# IBus_BMW_DAC_Test.net
KiCad netlist of a schematic drawn in EasyEDA
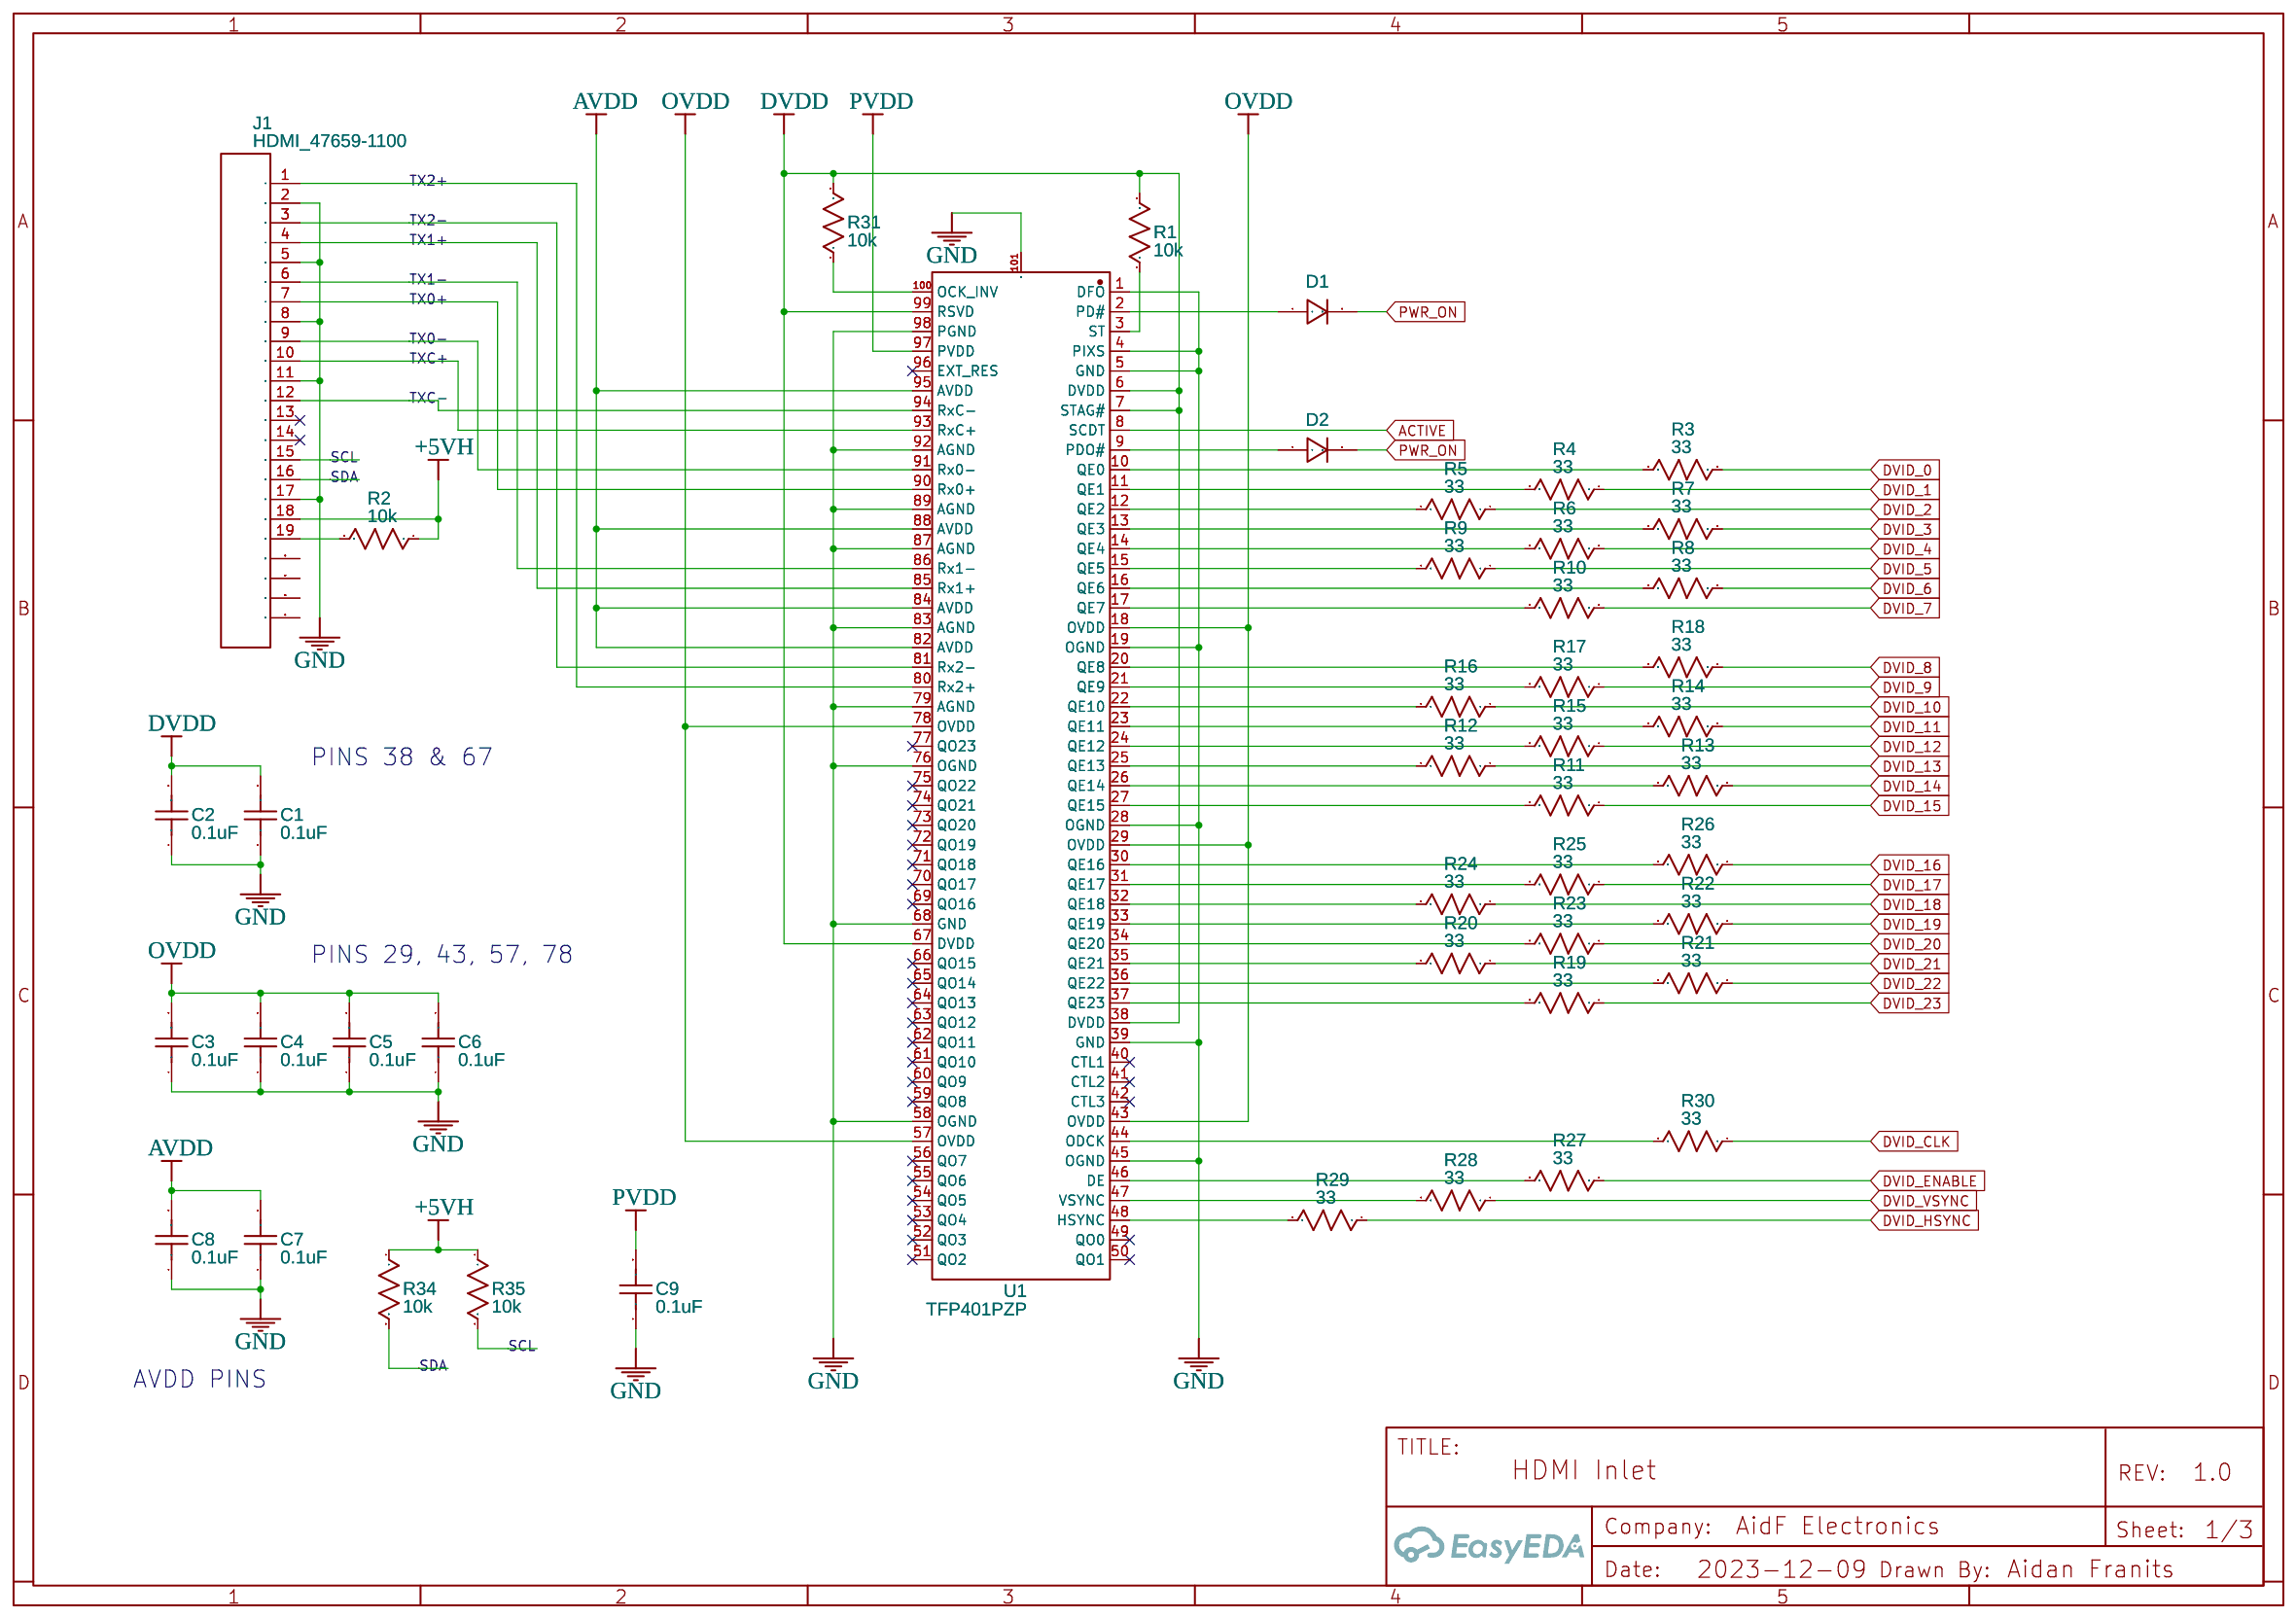
[diagram p0: HDMI Inlet]
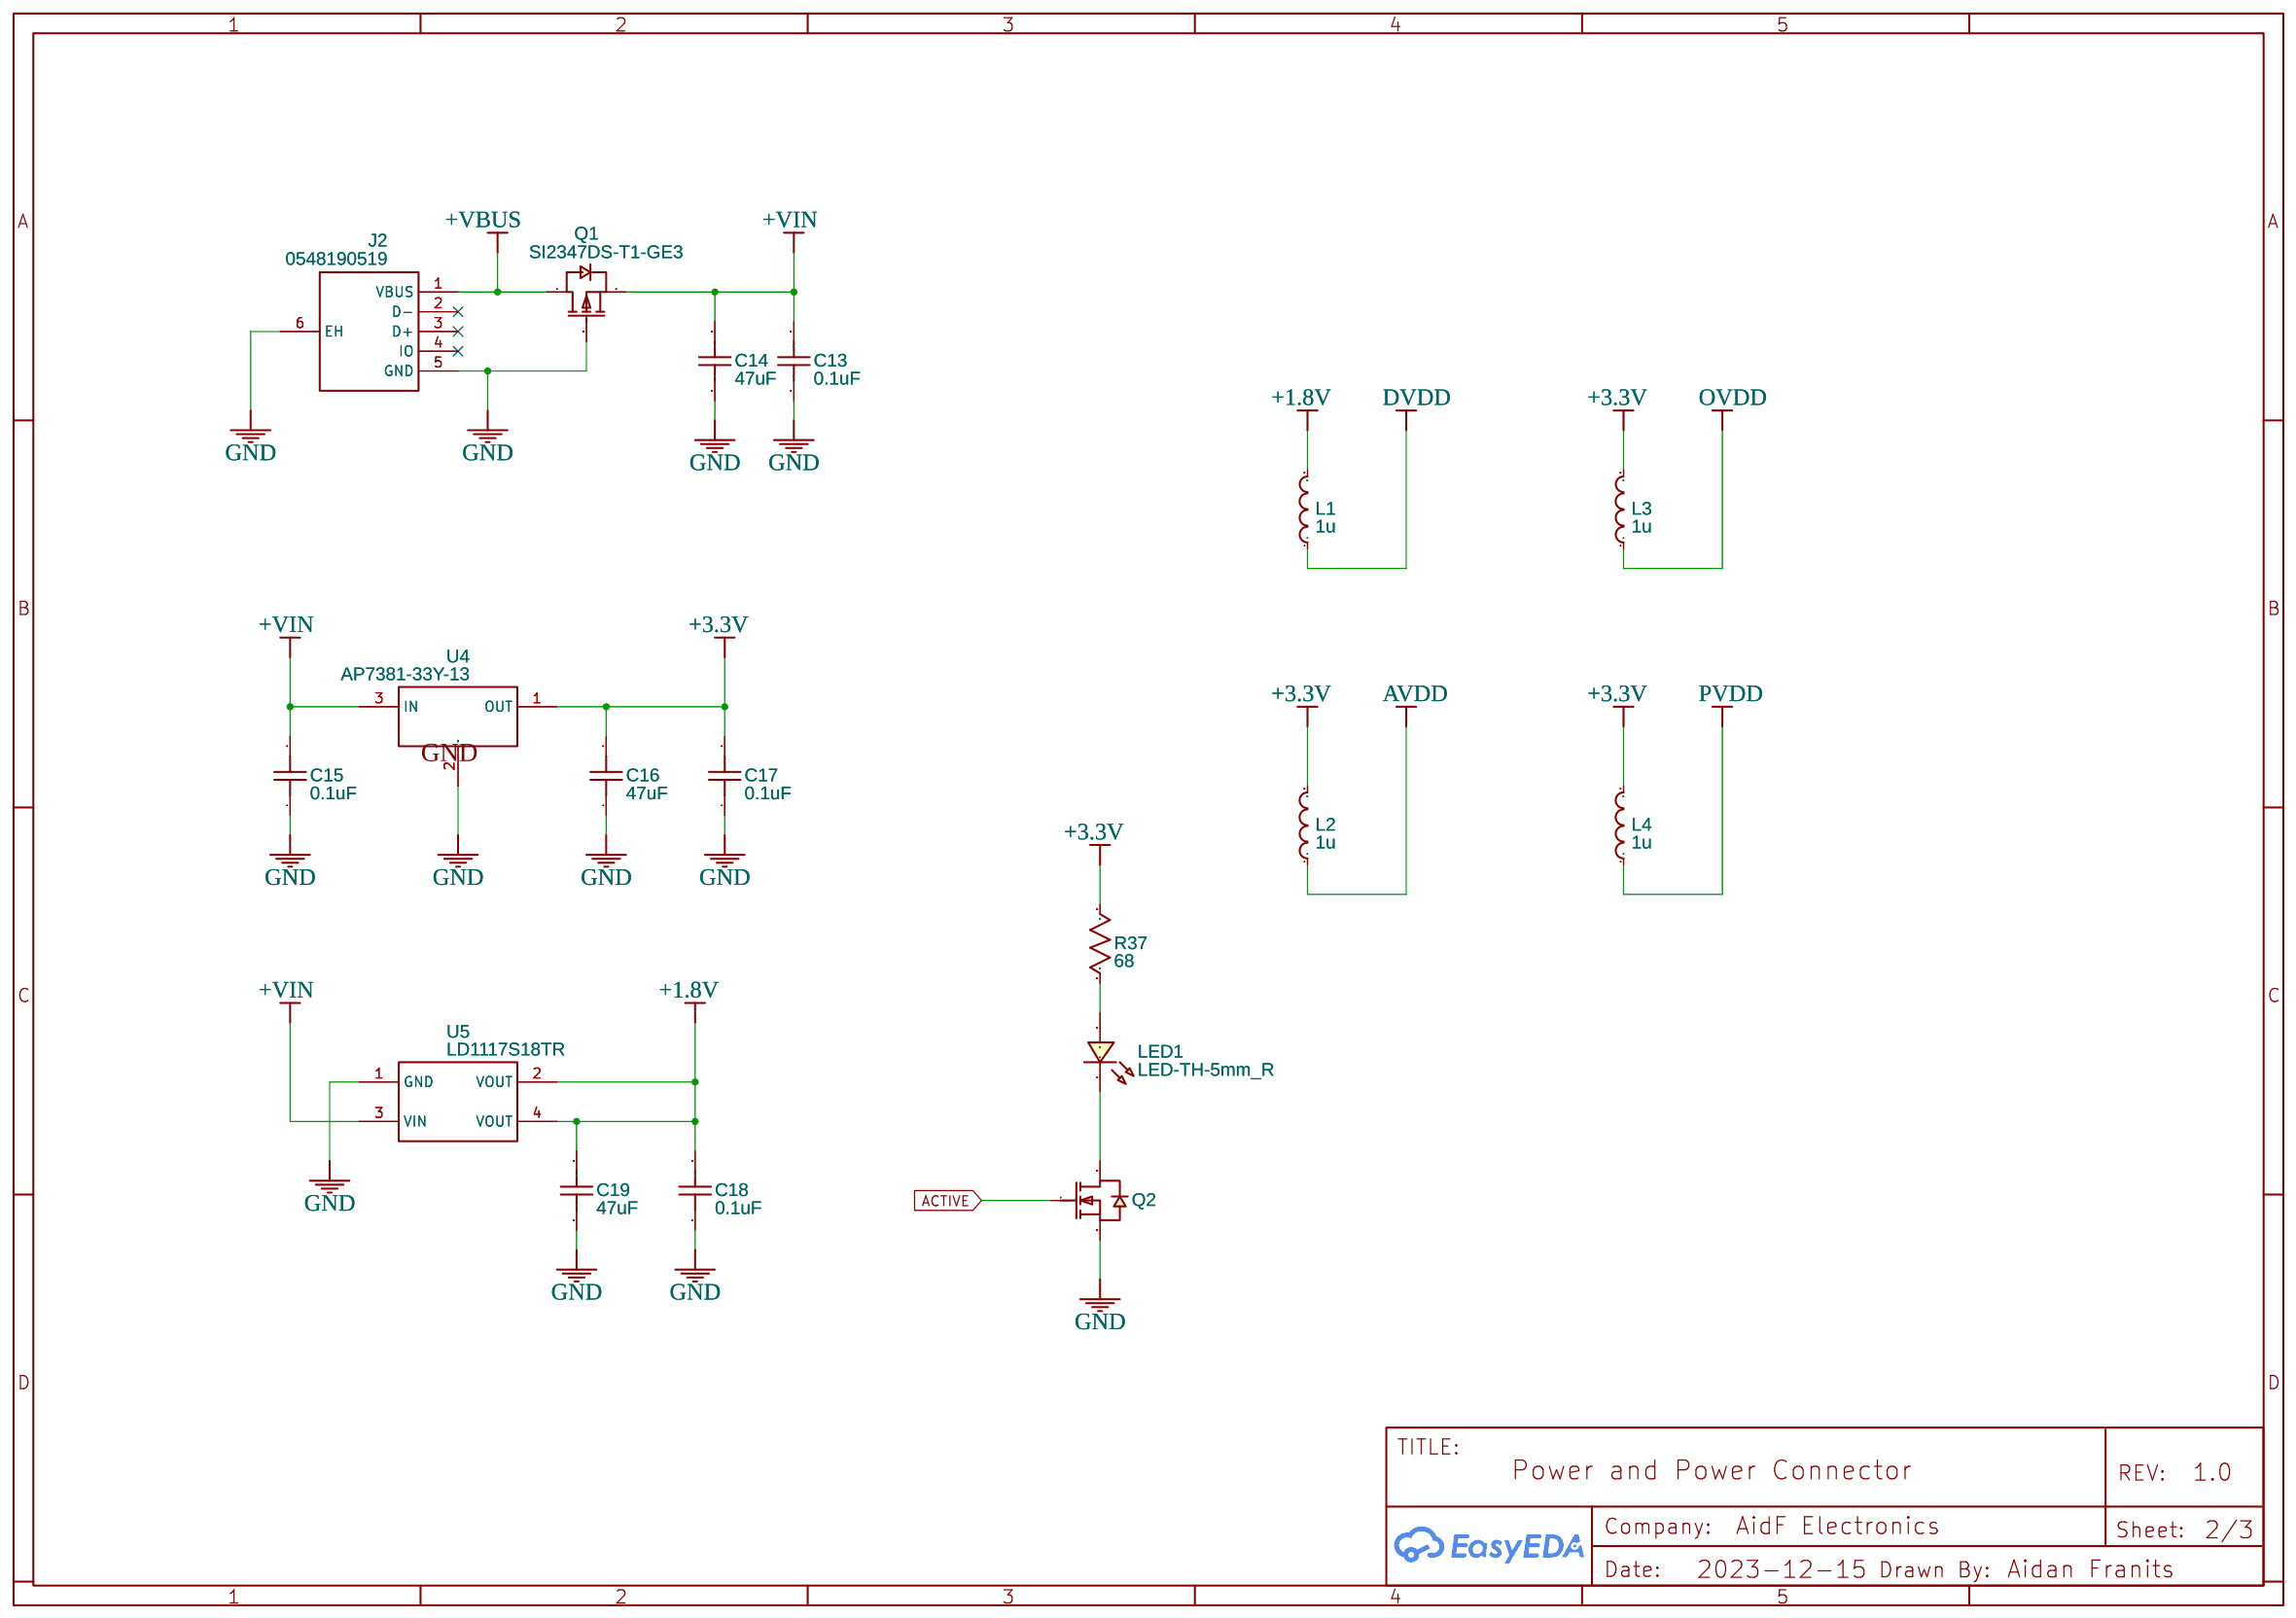
[diagram p1: Power and Power Connector]
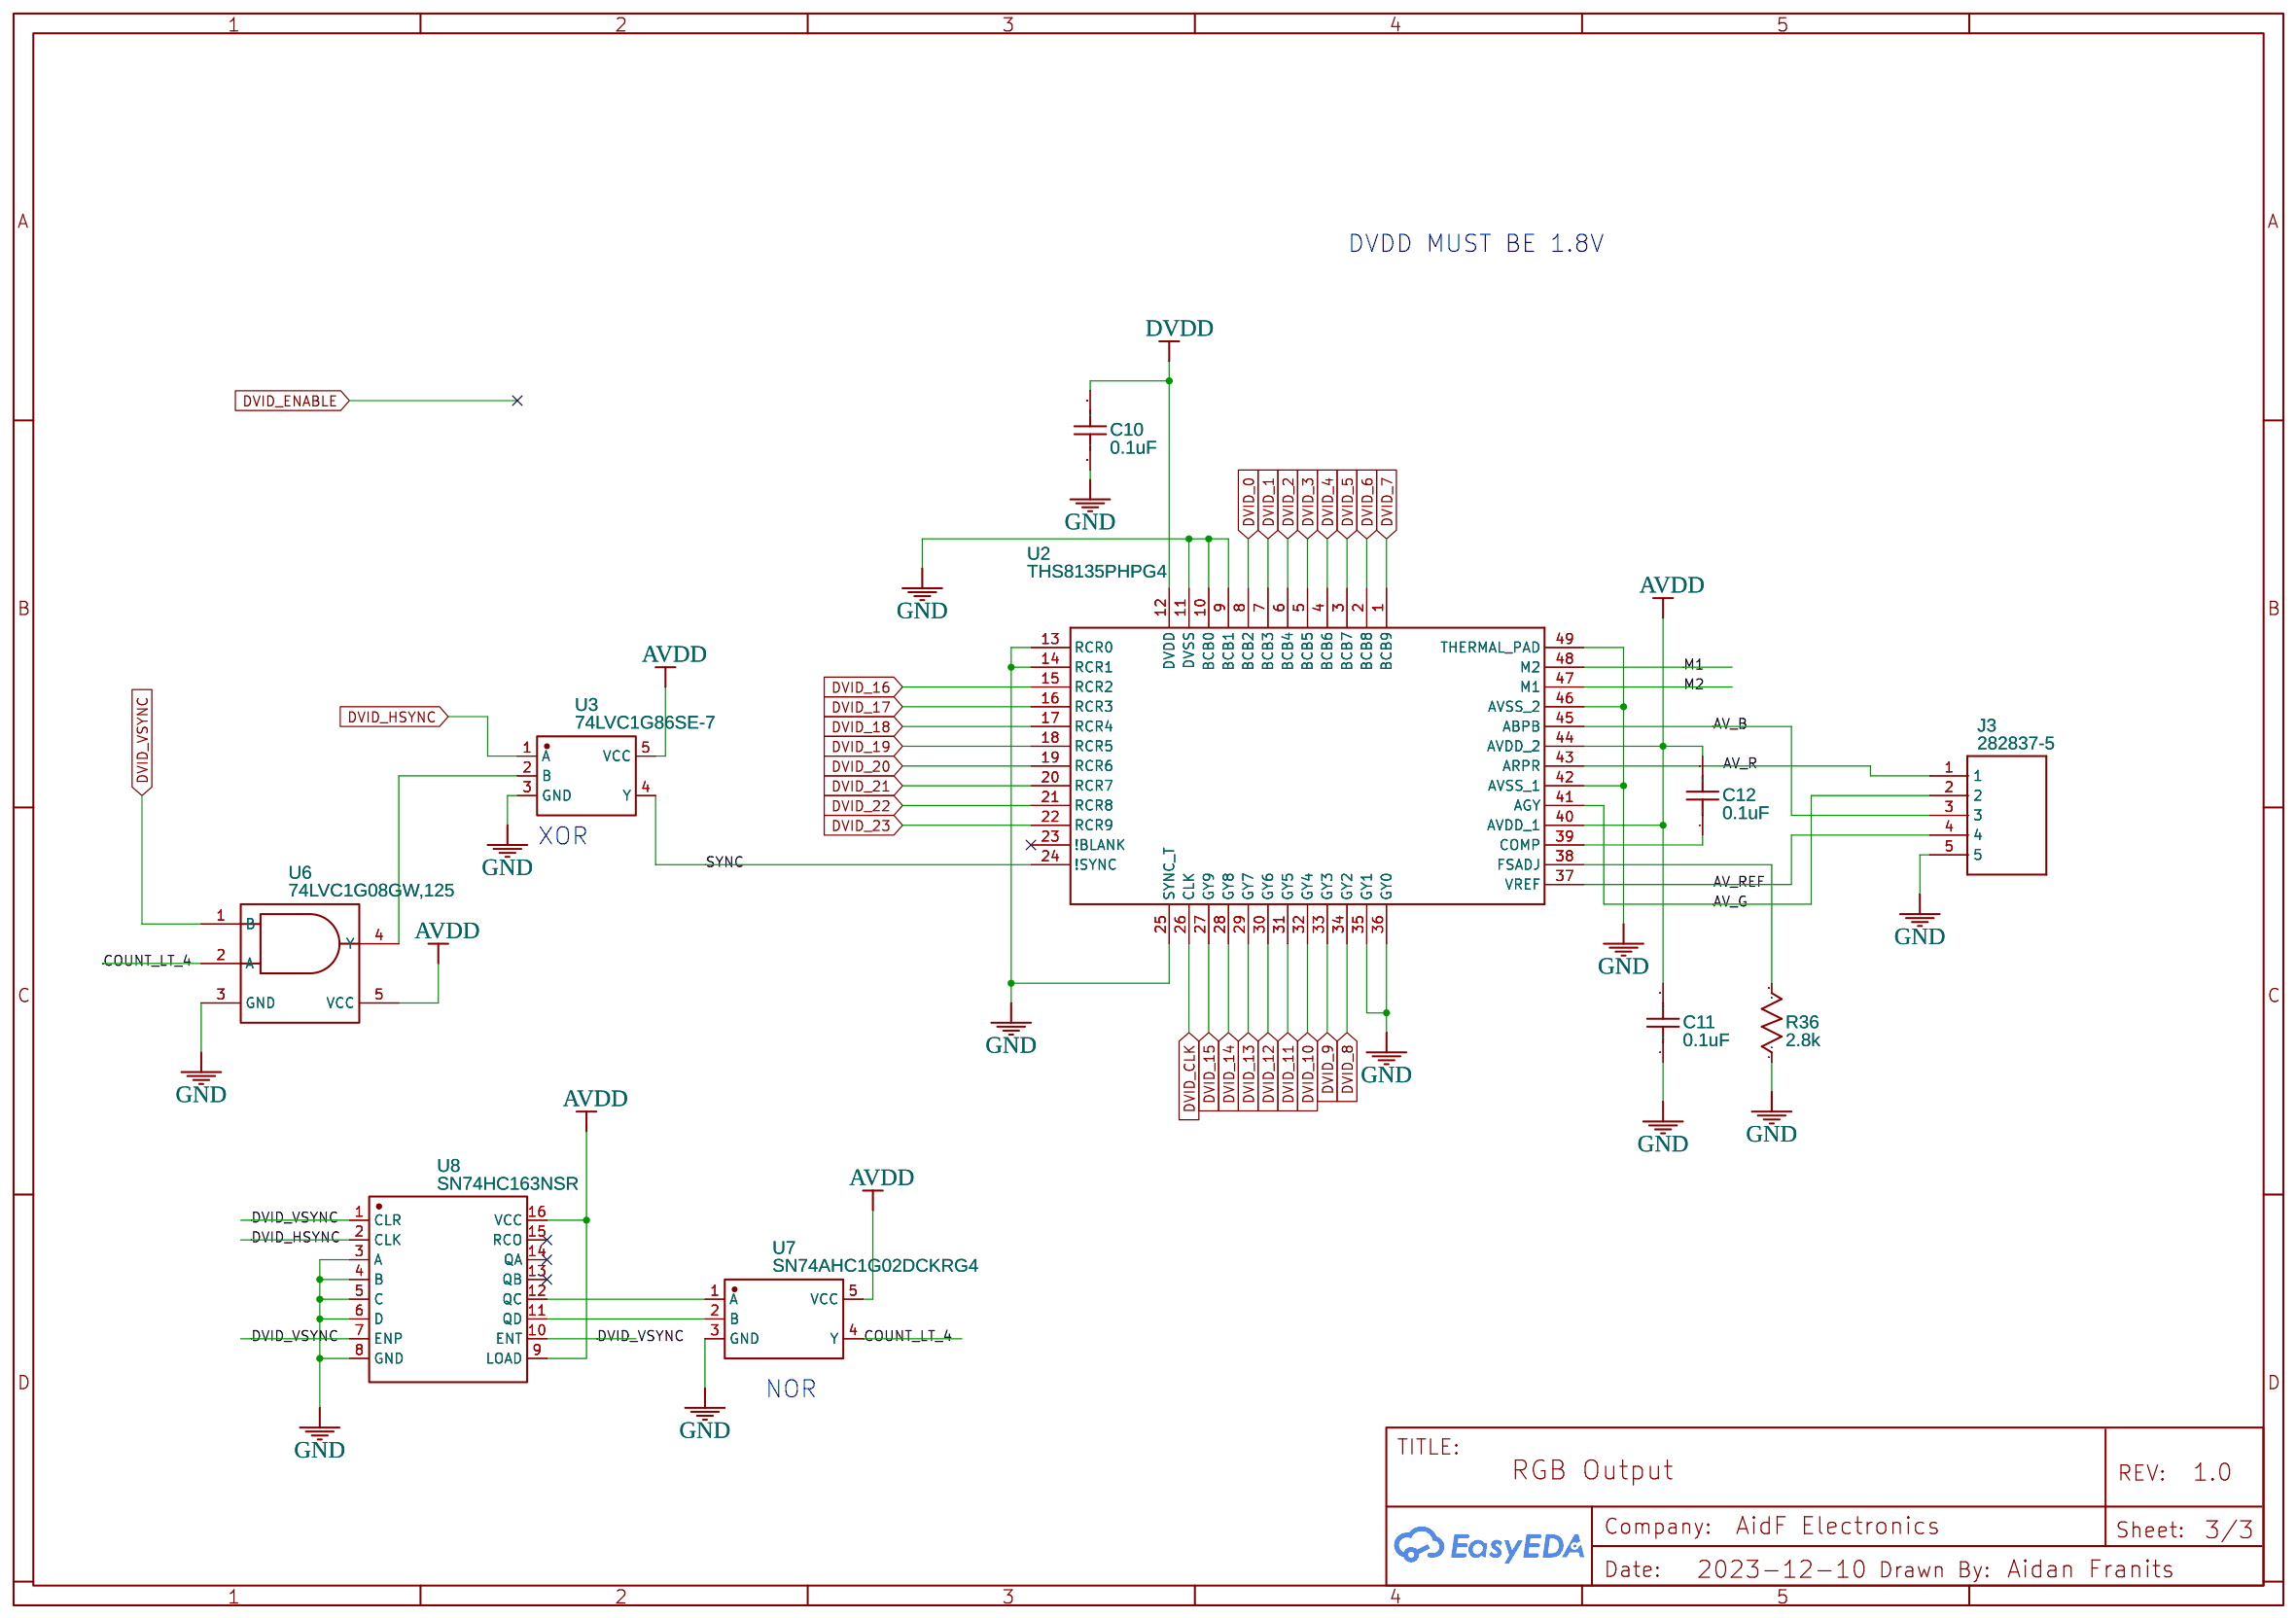
[diagram p2: RGB Output]

(export (version "E")
  (design (tool "Eeschema 10.0.6"))
  (components
    (comp (ref "C1")
      (value "0.1uF")
      (fields
        (field (name "Manufacturer Part") "0603B104K101CT")
        (field (name "Manufacturer") "Walsin Technology Corporation")
      )
      (libsource (lib "") (part "C_0603_US"))
    )
    (comp (ref "C2")
      (value "0.1uF")
      (fields
        (field (name "Manufacturer Part") "0603B104K101CT")
        (field (name "Manufacturer") "Walsin Technology Corporation")
      )
      (libsource (lib "") (part "C_0603_US"))
    )
    (comp (ref "C3")
      (value "0.1uF")
      (fields
        (field (name "Manufacturer Part") "0603B104K101CT")
        (field (name "Manufacturer") "Walsin Technology Corporation")
      )
      (libsource (lib "") (part "C_0603_US"))
    )
    (comp (ref "C4")
      (value "0.1uF")
      (fields
        (field (name "Manufacturer Part") "0603B104K101CT")
        (field (name "Manufacturer") "Walsin Technology Corporation")
      )
      (libsource (lib "") (part "C_0603_US"))
    )
    (comp (ref "C5")
      (value "0.1uF")
      (fields
        (field (name "Manufacturer Part") "0603B104K101CT")
        (field (name "Manufacturer") "Walsin Technology Corporation")
      )
      (libsource (lib "") (part "C_0603_US"))
    )
    (comp (ref "C6")
      (value "0.1uF")
      (fields
        (field (name "Manufacturer Part") "0603B104K101CT")
        (field (name "Manufacturer") "Walsin Technology Corporation")
      )
      (libsource (lib "") (part "C_0603_US"))
    )
    (comp (ref "C7")
      (value "0.1uF")
      (fields
        (field (name "Manufacturer Part") "0603B104K101CT")
        (field (name "Manufacturer") "Walsin Technology Corporation")
      )
      (libsource (lib "") (part "C_0603_US"))
    )
    (comp (ref "C8")
      (value "0.1uF")
      (fields
        (field (name "Manufacturer Part") "0603B104K101CT")
        (field (name "Manufacturer") "Walsin Technology Corporation")
      )
      (libsource (lib "") (part "C_0603_US"))
    )
    (comp (ref "C9")
      (value "0.1uF")
      (fields
        (field (name "Manufacturer Part") "0603B104K101CT")
        (field (name "Manufacturer") "Walsin Technology Corporation")
      )
      (libsource (lib "") (part "C_0603_US"))
    )
    (comp (ref "D1")
      (value "SD103AWS-TP")
      (fields (field (name "Manufacturer") "Micro Commercial Co"))
      (libsource (lib "") (part "1N4148"))
    )
    (comp (ref "D2")
      (value "SD103AWS-TP")
      (fields (field (name "Manufacturer") "Micro Commercial Co"))
      (libsource (lib "") (part "1N4148"))
    )
    (comp (ref "J1")
      (value "HDMI_47659-1100")
      (fields (field (name "Manufacturer Part") "2086581051") (field (name "Manufacturer") "Molex"))
      (libsource (lib "") (part "HDMI_47659-1100"))
    )
    (comp (ref "R1")
      (value "10k")
      (fields
        (field (name "Manufacturer Part") "ESR03EZPJ103")
        (field (name "Manufacturer") "Rohm Semiconductor")
      )
      (libsource (lib "") (part "R_0603_US_1"))
    )
    (comp (ref "R2")
      (value "10k")
      (fields
        (field (name "Manufacturer Part") "ESR03EZPJ103")
        (field (name "Manufacturer") "Rohm Semiconductor")
      )
      (libsource (lib "") (part "R_0603_US"))
    )
    (comp (ref "R3")
      (value "33")
      (fields
        (field (name "Manufacturer Part") "WR06X330 JTL")
        (field (name "Manufacturer") "Walsin Technology Corporation")
      )
      (libsource (lib "") (part "R_0603_US"))
    )
    (comp (ref "R4")
      (value "33")
      (fields
        (field (name "Manufacturer Part") "WR06X330 JTL")
        (field (name "Manufacturer") "Walsin Technology Corporation")
      )
      (libsource (lib "") (part "R_0603_US"))
    )
    (comp (ref "R5")
      (value "33")
      (fields
        (field (name "Manufacturer Part") "WR06X330 JTL")
        (field (name "Manufacturer") "Walsin Technology Corporation")
      )
      (libsource (lib "") (part "R_0603_US"))
    )
    (comp (ref "R6")
      (value "33")
      (fields
        (field (name "Manufacturer Part") "WR06X330 JTL")
        (field (name "Manufacturer") "Walsin Technology Corporation")
      )
      (libsource (lib "") (part "R_0603_US"))
    )
    (comp (ref "R7")
      (value "33")
      (fields
        (field (name "Manufacturer Part") "WR06X330 JTL")
        (field (name "Manufacturer") "Walsin Technology Corporation")
      )
      (libsource (lib "") (part "R_0603_US"))
    )
    (comp (ref "R8")
      (value "33")
      (fields
        (field (name "Manufacturer Part") "WR06X330 JTL")
        (field (name "Manufacturer") "Walsin Technology Corporation")
      )
      (libsource (lib "") (part "R_0603_US"))
    )
    (comp (ref "R9")
      (value "33")
      (fields
        (field (name "Manufacturer Part") "WR06X330 JTL")
        (field (name "Manufacturer") "Walsin Technology Corporation")
      )
      (libsource (lib "") (part "R_0603_US"))
    )
    (comp (ref "R10")
      (value "33")
      (fields
        (field (name "Manufacturer Part") "WR06X330 JTL")
        (field (name "Manufacturer") "Walsin Technology Corporation")
      )
      (libsource (lib "") (part "R_0603_US"))
    )
    (comp (ref "R11")
      (value "33")
      (fields
        (field (name "Manufacturer Part") "WR06X330 JTL")
        (field (name "Manufacturer") "Walsin Technology Corporation")
      )
      (libsource (lib "") (part "R_0603_US"))
    )
    (comp (ref "R12")
      (value "33")
      (fields
        (field (name "Manufacturer Part") "WR06X330 JTL")
        (field (name "Manufacturer") "Walsin Technology Corporation")
      )
      (libsource (lib "") (part "R_0603_US"))
    )
    (comp (ref "R13")
      (value "33")
      (fields
        (field (name "Manufacturer Part") "WR06X330 JTL")
        (field (name "Manufacturer") "Walsin Technology Corporation")
      )
      (libsource (lib "") (part "R_0603_US"))
    )
    (comp (ref "R14")
      (value "33")
      (fields
        (field (name "Manufacturer Part") "WR06X330 JTL")
        (field (name "Manufacturer") "Walsin Technology Corporation")
      )
      (libsource (lib "") (part "R_0603_US"))
    )
    (comp (ref "R15")
      (value "33")
      (fields
        (field (name "Manufacturer Part") "WR06X330 JTL")
        (field (name "Manufacturer") "Walsin Technology Corporation")
      )
      (libsource (lib "") (part "R_0603_US"))
    )
    (comp (ref "R16")
      (value "33")
      (fields
        (field (name "Manufacturer Part") "WR06X330 JTL")
        (field (name "Manufacturer") "Walsin Technology Corporation")
      )
      (libsource (lib "") (part "R_0603_US"))
    )
    (comp (ref "R17")
      (value "33")
      (fields
        (field (name "Manufacturer Part") "WR06X330 JTL")
        (field (name "Manufacturer") "Walsin Technology Corporation")
      )
      (libsource (lib "") (part "R_0603_US"))
    )
    (comp (ref "R18")
      (value "33")
      (fields
        (field (name "Manufacturer Part") "WR06X330 JTL")
        (field (name "Manufacturer") "Walsin Technology Corporation")
      )
      (libsource (lib "") (part "R_0603_US"))
    )
    (comp (ref "R19")
      (value "33")
      (fields
        (field (name "Manufacturer Part") "WR06X330 JTL")
        (field (name "Manufacturer") "Walsin Technology Corporation")
      )
      (libsource (lib "") (part "R_0603_US"))
    )
    (comp (ref "R20")
      (value "33")
      (fields
        (field (name "Manufacturer Part") "WR06X330 JTL")
        (field (name "Manufacturer") "Walsin Technology Corporation")
      )
      (libsource (lib "") (part "R_0603_US"))
    )
    (comp (ref "R21")
      (value "33")
      (fields
        (field (name "Manufacturer Part") "WR06X330 JTL")
        (field (name "Manufacturer") "Walsin Technology Corporation")
      )
      (libsource (lib "") (part "R_0603_US"))
    )
    (comp (ref "R22")
      (value "33")
      (fields
        (field (name "Manufacturer Part") "WR06X330 JTL")
        (field (name "Manufacturer") "Walsin Technology Corporation")
      )
      (libsource (lib "") (part "R_0603_US"))
    )
    (comp (ref "R23")
      (value "33")
      (fields
        (field (name "Manufacturer Part") "WR06X330 JTL")
        (field (name "Manufacturer") "Walsin Technology Corporation")
      )
      (libsource (lib "") (part "R_0603_US"))
    )
    (comp (ref "R24")
      (value "33")
      (fields
        (field (name "Manufacturer Part") "WR06X330 JTL")
        (field (name "Manufacturer") "Walsin Technology Corporation")
      )
      (libsource (lib "") (part "R_0603_US"))
    )
    (comp (ref "R25")
      (value "33")
      (fields
        (field (name "Manufacturer Part") "WR06X330 JTL")
        (field (name "Manufacturer") "Walsin Technology Corporation")
      )
      (libsource (lib "") (part "R_0603_US"))
    )
    (comp (ref "R26")
      (value "33")
      (fields
        (field (name "Manufacturer Part") "WR06X330 JTL")
        (field (name "Manufacturer") "Walsin Technology Corporation")
      )
      (libsource (lib "") (part "R_0603_US"))
    )
    (comp (ref "R27")
      (value "33")
      (fields
        (field (name "Manufacturer Part") "WR06X330 JTL")
        (field (name "Manufacturer") "Walsin Technology Corporation")
      )
      (libsource (lib "") (part "R_0603_US"))
    )
    (comp (ref "R28")
      (value "33")
      (fields
        (field (name "Manufacturer Part") "WR06X330 JTL")
        (field (name "Manufacturer") "Walsin Technology Corporation")
      )
      (libsource (lib "") (part "R_0603_US"))
    )
    (comp (ref "R29")
      (value "33")
      (fields
        (field (name "Manufacturer Part") "WR06X330 JTL")
        (field (name "Manufacturer") "Walsin Technology Corporation")
      )
      (libsource (lib "") (part "R_0603_US"))
    )
    (comp (ref "R30")
      (value "33")
      (fields
        (field (name "Manufacturer Part") "WR06X330 JTL")
        (field (name "Manufacturer") "Walsin Technology Corporation")
      )
      (libsource (lib "") (part "R_0603_US"))
    )
    (comp (ref "R31")
      (value "10k")
      (fields
        (field (name "Manufacturer Part") "ESR03EZPJ103")
        (field (name "Manufacturer") "Rohm Semiconductor")
      )
      (libsource (lib "") (part "R_0603_US_1"))
    )
    (comp (ref "R34")
      (value "10k")
      (fields
        (field (name "Manufacturer Part") "ESR03EZPJ103")
        (field (name "Manufacturer") "Rohm Semiconductor")
      )
      (libsource (lib "") (part "R_0603_US_2"))
    )
    (comp (ref "R35")
      (value "10k")
      (fields
        (field (name "Manufacturer Part") "ESR03EZPJ103")
        (field (name "Manufacturer") "Rohm Semiconductor")
      )
      (libsource (lib "") (part "R_0603_US_2"))
    )
    (comp (ref "U1")
      (value "TFP401PZP")
      (fields (field (name "Manufacturer") "Texas Instruments"))
      (libsource (lib "") (part "TFP401PZP"))
    )
    (comp (ref "C13")
      (value "0.1uF")
      (fields
        (field (name "Manufacturer Part") "0603B104K101CT")
        (field (name "Manufacturer") "Walsin Technology Corporation")
      )
      (libsource (lib "") (part "C_0603_US"))
    )
    (comp (ref "C14")
      (value "47uF")
      (fields
        (field (name "Manufacturer Part") "GRM31CR61E476ME44K")
        (field (name "Manufacturer") "Murata Electronics")
      )
      (libsource (lib "") (part "C_0603_US"))
    )
    (comp (ref "C15")
      (value "0.1uF")
      (fields
        (field (name "Manufacturer Part") "0603B104K101CT")
        (field (name "Manufacturer") "Walsin Technology Corporation")
      )
      (libsource (lib "") (part "C_0603_US"))
    )
    (comp (ref "C16")
      (value "47uF")
      (fields
        (field (name "Manufacturer Part") "GRM31CR61E476ME44K")
        (field (name "Manufacturer") "Murata Electronics")
      )
      (libsource (lib "") (part "C_0603_US"))
    )
    (comp (ref "C17")
      (value "0.1uF")
      (fields
        (field (name "Manufacturer Part") "0603B104K101CT")
        (field (name "Manufacturer") "Walsin Technology Corporation")
      )
      (libsource (lib "") (part "C_0603_US"))
    )
    (comp (ref "C18")
      (value "0.1uF")
      (fields
        (field (name "Manufacturer Part") "0603B104K101CT")
        (field (name "Manufacturer") "Walsin Technology Corporation")
      )
      (libsource (lib "") (part "C_0603_US"))
    )
    (comp (ref "C19")
      (value "47uF")
      (fields
        (field (name "Manufacturer Part") "GRM31CR61E476ME44K")
        (field (name "Manufacturer") "Murata Electronics")
      )
      (libsource (lib "") (part "C_0603_US"))
    )
    (comp (ref "J2")
      (value "0548190519")
      (fields (field (name "Manufacturer") "Molex"))
      (libsource (lib "") (part "0548190519"))
    )
    (comp (ref "L1")
      (value "1u")
      (fields
        (field (name "Manufacturer Part") "BLM18RK601SN1D")
        (field (name "Manufacturer") "Murata Electronics")
      )
      (libsource (lib "") (part "L0603_US_1"))
    )
    (comp (ref "L2")
      (value "1u")
      (fields
        (field (name "Manufacturer Part") "BLM18RK601SN1D")
        (field (name "Manufacturer") "Murata Electronics")
      )
      (libsource (lib "") (part "L0603_US"))
    )
    (comp (ref "L3")
      (value "1u")
      (fields
        (field (name "Manufacturer Part") "BLM18RK601SN1D")
        (field (name "Manufacturer") "Murata Electronics")
      )
      (libsource (lib "") (part "L0603_US_1"))
    )
    (comp (ref "L4")
      (value "1u")
      (fields
        (field (name "Manufacturer Part") "BLM18RK601SN1D")
        (field (name "Manufacturer") "Murata Electronics")
      )
      (libsource (lib "") (part "L0603_US"))
    )
    (comp (ref "LED1") (value "LED-TH-5mm_R") (libsource (lib "") (part "LED-TH-5mm_R")))
    (comp (ref "Q1")
      (value "SI2347DS-T1-GE3")
      (fields (field (name "Manufacturer") "Vishay Siliconix"))
      (libsource (lib "") (part "IRF5210"))
    )
    (comp (ref "Q2")
      (value "DMN67D8LW-13")
      (fields (field (name "Manufacturer") "Diodes Incorporated"))
      (libsource (lib "") (part "2N7002"))
    )
    (comp (ref "R37")
      (value "68")
      (fields
        (field (name "Manufacturer Part") "WR06X680 JTL")
        (field (name "Manufacturer") "Walsin Technology Corporation")
      )
      (libsource (lib "") (part "R_0603_US"))
    )
    (comp (ref "U4")
      (value "AP7381-33Y-13")
      (fields
        (field (name "Manufacturer Part") "AP7370-33Y-13")
        (field (name "Manufacturer") "Diodes Incorporated")
      )
      (libsource (lib "") (part "AP7381-33Y-13"))
    )
    (comp (ref "U5")
      (value "LD1117S18TR")
      (fields (field (name "Manufacturer") "STMicroelectronics"))
      (libsource (lib "") (part "LD1117S18TR"))
    )
    (comp (ref "C10")
      (value "0.1uF")
      (fields
        (field (name "Manufacturer Part") "0603B104K101CT")
        (field (name "Manufacturer") "Walsin Technology Corporation")
      )
      (libsource (lib "") (part "C_0603_US"))
    )
    (comp (ref "C11")
      (value "0.1uF")
      (fields
        (field (name "Manufacturer Part") "0603B104K101CT")
        (field (name "Manufacturer") "Walsin Technology Corporation")
      )
      (libsource (lib "") (part "C_0603_US"))
    )
    (comp (ref "C12")
      (value "0.1uF")
      (fields
        (field (name "Manufacturer Part") "0603B104K101CT")
        (field (name "Manufacturer") "Walsin Technology Corporation")
      )
      (libsource (lib "") (part "C_0603_US"))
    )
    (comp (ref "J3")
      (value "282837-5")
      (fields (field (name "Manufacturer") "TE Connectivity AMP Connectors"))
      (libsource (lib "") (part "282837-5"))
    )
    (comp (ref "R36")
      (value "2.8k")
      (fields
        (field (name "Manufacturer Part") "RMCF0603FT2K80")
        (field (name "Manufacturer") "Stackpole Electronics Inc")
      )
      (libsource (lib "") (part "R_0603_US"))
    )
    (comp (ref "U2")
      (value "THS8135PHPG4")
      (fields
        (field (name "Manufacturer Part") "THS8135PHP")
        (field (name "Manufacturer") "Texas Instruments")
      )
      (libsource (lib "") (part "THS8135PHPG4"))
    )
    (comp (ref "U3")
      (value "74LVC1G86SE-7")
      (fields (field (name "Manufacturer") "Diodes Incorporated"))
      (libsource (lib "") (part "74LVC1G86SE-7"))
    )
    (comp (ref "U6")
      (value "74LVC1G08GW,125")
      (fields (field (name "Manufacturer") "Nexperia USA Inc."))
      (libsource (lib "") (part "74LVC1G08GW,125"))
    )
    (comp (ref "U7")
      (value "SN74AHC1G02DCKRG4")
      (fields (field (name "Manufacturer") "TI(德州仪器)"))
      (libsource (lib "") (part "SN74AHC1G02DCKRG4"))
    )
    (comp (ref "U8")
      (value "SN74HC163NSR")
      (fields (field (name "Manufacturer") "Texas Instruments"))
      (libsource (lib "") (part "SN74HC163NSR"))
    )
  )
  (nets
    (net (code "1") (name "+1.8V") (class "Default")
      (node (ref "C18") (pin "2") (pinfunction "2_2") (pintype "unspecified"))
      (node (ref "C19") (pin "2") (pinfunction "2_2") (pintype "unspecified"))
      (node (ref "L1") (pin "2") (pinfunction "2_2") (pintype "unspecified"))
      (node (ref "U5") (pin "2") (pinfunction "VOUT_2") (pintype "unspecified"))
      (node (ref "U5") (pin "4") (pinfunction "VOUT_4") (pintype "unspecified"))
    )
    (net (code "2") (name "+3.3V") (class "Default")
      (node (ref "C16") (pin "2") (pinfunction "2_2") (pintype "unspecified"))
      (node (ref "C17") (pin "2") (pinfunction "2_2") (pintype "unspecified"))
      (node (ref "L2") (pin "2") (pinfunction "2_2") (pintype "unspecified"))
      (node (ref "L3") (pin "2") (pinfunction "2_2") (pintype "unspecified"))
      (node (ref "L4") (pin "2") (pinfunction "2_2") (pintype "unspecified"))
      (node (ref "R37") (pin "1") (pinfunction "1_1") (pintype "unspecified"))
      (node (ref "U4") (pin "1") (pinfunction "OUT_1") (pintype "passive"))
    )
    (net (code "3") (name "+5VH") (class "Default")
      (node (ref "J1") (pin "18") (pinfunction "18_18") (pintype "bidirectional"))
      (node (ref "R2") (pin "1") (pinfunction "1_1") (pintype "unspecified"))
      (node (ref "R34") (pin "1") (pinfunction "1_1") (pintype "unspecified"))
      (node (ref "R35") (pin "1") (pinfunction "1_1") (pintype "unspecified"))
    )
    (net (code "4") (name "+VBUS") (class "Default")
      (node (ref "J2") (pin "1") (pinfunction "VBUS_1") (pintype "unspecified"))
      (node (ref "Q1") (pin "3") (pinfunction "D_3") (pintype "unspecified"))
    )
    (net (code "5") (name "+VIN") (class "Default")
      (node (ref "C13") (pin "2") (pinfunction "2_2") (pintype "unspecified"))
      (node (ref "C14") (pin "2") (pinfunction "2_2") (pintype "unspecified"))
      (node (ref "C15") (pin "2") (pinfunction "2_2") (pintype "unspecified"))
      (node (ref "Q1") (pin "2") (pinfunction "S_2") (pintype "unspecified"))
      (node (ref "U4") (pin "3") (pinfunction "IN_3") (pintype "passive"))
      (node (ref "U5") (pin "3") (pinfunction "VIN_3") (pintype "unspecified"))
    )
    (net (code "6") (name "ACTIVE") (class "Default")
      (node (ref "Q2") (pin "1") (pinfunction "G_1") (pintype "unspecified"))
      (node (ref "U1") (pin "8") (pinfunction "SCDT_8") (pintype "unspecified"))
    )
    (net (code "7") (name "AVDD") (class "Default")
      (node (ref "C11") (pin "2") (pinfunction "2_2") (pintype "unspecified"))
      (node (ref "C12") (pin "2") (pinfunction "2_2") (pintype "unspecified"))
      (node (ref "C7") (pin "2") (pinfunction "2_2") (pintype "unspecified"))
      (node (ref "C8") (pin "2") (pinfunction "2_2") (pintype "unspecified"))
      (node (ref "L2") (pin "1") (pinfunction "1_1") (pintype "unspecified"))
      (node (ref "U1") (pin "82") (pinfunction "AVDD_82") (pintype "unspecified"))
      (node (ref "U1") (pin "84") (pinfunction "AVDD_84") (pintype "unspecified"))
      (node (ref "U1") (pin "88") (pinfunction "AVDD_88") (pintype "unspecified"))
      (node (ref "U1") (pin "95") (pinfunction "AVDD_95") (pintype "unspecified"))
      (node (ref "U2") (pin "40") (pinfunction "AVDD_1_40") (pintype "bidirectional"))
      (node (ref "U2") (pin "44") (pinfunction "AVDD_2_44") (pintype "bidirectional"))
      (node (ref "U3") (pin "5") (pinfunction "VCC_5") (pintype "unspecified"))
      (node (ref "U6") (pin "5") (pinfunction "VCC_5") (pintype "unspecified"))
      (node (ref "U7") (pin "5") (pinfunction "VCC_5") (pintype "unspecified"))
      (node (ref "U8") (pin "16") (pinfunction "VCC_16") (pintype "unspecified"))
      (node (ref "U8") (pin "9") (pinfunction "LOAD_9") (pintype "unspecified"))
    )
    (net (code "8") (name "AV_B") (class "Default")
      (node (ref "J3") (pin "3") (pinfunction "3_3") (pintype "bidirectional"))
      (node (ref "U2") (pin "45") (pinfunction "ABPB_45") (pintype "bidirectional"))
    )
    (net (code "9") (name "AV_G") (class "Default")
      (node (ref "J3") (pin "2") (pinfunction "2_2") (pintype "bidirectional"))
      (node (ref "U2") (pin "41") (pinfunction "AGY_41") (pintype "bidirectional"))
    )
    (net (code "10") (name "AV_R") (class "Default")
      (node (ref "J3") (pin "1") (pinfunction "1_1") (pintype "bidirectional"))
      (node (ref "U2") (pin "43") (pinfunction "ARPR_43") (pintype "bidirectional"))
    )
    (net (code "11") (name "AV_REF") (class "Default")
      (node (ref "J3") (pin "4") (pinfunction "4_4") (pintype "bidirectional"))
      (node (ref "U2") (pin "37") (pinfunction "VREF_37") (pintype "bidirectional"))
    )
    (net (code "12") (name "COUNT_LT_4") (class "Default")
      (node (ref "U6") (pin "2") (pinfunction "A_2") (pintype "unspecified"))
      (node (ref "U7") (pin "4") (pinfunction "Y_4") (pintype "unspecified"))
    )
    (net (code "13") (name "DVDD") (class "Default")
      (node (ref "C1") (pin "2") (pinfunction "2_2") (pintype "unspecified"))
      (node (ref "C10") (pin "2") (pinfunction "2_2") (pintype "unspecified"))
      (node (ref "C2") (pin "2") (pinfunction "2_2") (pintype "unspecified"))
      (node (ref "L1") (pin "1") (pinfunction "1_1") (pintype "unspecified"))
      (node (ref "R1") (pin "2") (pinfunction "2_2") (pintype "unspecified"))
      (node (ref "R31") (pin "2") (pinfunction "2_2") (pintype "unspecified"))
      (node (ref "U1") (pin "38") (pinfunction "DVDD_38") (pintype "unspecified"))
      (node (ref "U1") (pin "6") (pinfunction "DVDD_6") (pintype "unspecified"))
      (node (ref "U1") (pin "67") (pinfunction "DVDD_67") (pintype "unspecified"))
      (node (ref "U1") (pin "7") (pinfunction "STAG#_7") (pintype "unspecified"))
      (node (ref "U1") (pin "99") (pinfunction "RSVD_99") (pintype "unspecified"))
      (node (ref "U2") (pin "12") (pinfunction "DVDD_12") (pintype "bidirectional"))
    )
    (net (code "14") (name "DVID_0") (class "Default")
      (node (ref "R3") (pin "1") (pinfunction "1_1") (pintype "unspecified"))
      (node (ref "U2") (pin "8") (pinfunction "BCB2_8") (pintype "bidirectional"))
    )
    (net (code "15") (name "DVID_1") (class "Default")
      (node (ref "R4") (pin "1") (pinfunction "1_1") (pintype "unspecified"))
      (node (ref "U2") (pin "7") (pinfunction "BCB3_7") (pintype "bidirectional"))
    )
    (net (code "16") (name "DVID_2") (class "Default")
      (node (ref "R5") (pin "1") (pinfunction "1_1") (pintype "unspecified"))
      (node (ref "U2") (pin "6") (pinfunction "BCB4_6") (pintype "bidirectional"))
    )
    (net (code "17") (name "DVID_3") (class "Default")
      (node (ref "R7") (pin "1") (pinfunction "1_1") (pintype "unspecified"))
      (node (ref "U2") (pin "5") (pinfunction "BCB5_5") (pintype "bidirectional"))
    )
    (net (code "18") (name "DVID_4") (class "Default")
      (node (ref "R6") (pin "1") (pinfunction "1_1") (pintype "unspecified"))
      (node (ref "U2") (pin "4") (pinfunction "BCB6_4") (pintype "bidirectional"))
    )
    (net (code "19") (name "DVID_5") (class "Default")
      (node (ref "R9") (pin "1") (pinfunction "1_1") (pintype "unspecified"))
      (node (ref "U2") (pin "3") (pinfunction "BCB7_3") (pintype "bidirectional"))
    )
    (net (code "20") (name "DVID_6") (class "Default")
      (node (ref "R8") (pin "1") (pinfunction "1_1") (pintype "unspecified"))
      (node (ref "U2") (pin "2") (pinfunction "BCB8_2") (pintype "bidirectional"))
    )
    (net (code "21") (name "DVID_7") (class "Default")
      (node (ref "R10") (pin "1") (pinfunction "1_1") (pintype "unspecified"))
      (node (ref "U2") (pin "1") (pinfunction "BCB9_1") (pintype "bidirectional"))
    )
    (net (code "22") (name "DVID_8") (class "Default")
      (node (ref "R18") (pin "1") (pinfunction "1_1") (pintype "unspecified"))
      (node (ref "U2") (pin "34") (pinfunction "GY2_34") (pintype "bidirectional"))
    )
    (net (code "23") (name "DVID_9") (class "Default")
      (node (ref "R17") (pin "1") (pinfunction "1_1") (pintype "unspecified"))
      (node (ref "U2") (pin "33") (pinfunction "GY3_33") (pintype "bidirectional"))
    )
    (net (code "24") (name "DVID_10") (class "Default")
      (node (ref "R16") (pin "1") (pinfunction "1_1") (pintype "unspecified"))
      (node (ref "U2") (pin "32") (pinfunction "GY4_32") (pintype "bidirectional"))
    )
    (net (code "25") (name "DVID_11") (class "Default")
      (node (ref "R14") (pin "1") (pinfunction "1_1") (pintype "unspecified"))
      (node (ref "U2") (pin "31") (pinfunction "GY5_31") (pintype "bidirectional"))
    )
    (net (code "26") (name "DVID_12") (class "Default")
      (node (ref "R15") (pin "1") (pinfunction "1_1") (pintype "unspecified"))
      (node (ref "U2") (pin "30") (pinfunction "GY6_30") (pintype "bidirectional"))
    )
    (net (code "27") (name "DVID_13") (class "Default")
      (node (ref "R12") (pin "1") (pinfunction "1_1") (pintype "unspecified"))
      (node (ref "U2") (pin "29") (pinfunction "GY7_29") (pintype "bidirectional"))
    )
    (net (code "28") (name "DVID_14") (class "Default")
      (node (ref "R13") (pin "1") (pinfunction "1_1") (pintype "unspecified"))
      (node (ref "U2") (pin "28") (pinfunction "GY8_28") (pintype "bidirectional"))
    )
    (net (code "29") (name "DVID_15") (class "Default")
      (node (ref "R11") (pin "1") (pinfunction "1_1") (pintype "unspecified"))
      (node (ref "U2") (pin "27") (pinfunction "GY9_27") (pintype "bidirectional"))
    )
    (net (code "30") (name "DVID_16") (class "Default")
      (node (ref "R26") (pin "1") (pinfunction "1_1") (pintype "unspecified"))
      (node (ref "U2") (pin "15") (pinfunction "RCR2_15") (pintype "bidirectional"))
    )
    (net (code "31") (name "DVID_17") (class "Default")
      (node (ref "R25") (pin "1") (pinfunction "1_1") (pintype "unspecified"))
      (node (ref "U2") (pin "16") (pinfunction "RCR3_16") (pintype "bidirectional"))
    )
    (net (code "32") (name "DVID_18") (class "Default")
      (node (ref "R24") (pin "1") (pinfunction "1_1") (pintype "unspecified"))
      (node (ref "U2") (pin "17") (pinfunction "RCR4_17") (pintype "bidirectional"))
    )
    (net (code "33") (name "DVID_19") (class "Default")
      (node (ref "R22") (pin "1") (pinfunction "1_1") (pintype "unspecified"))
      (node (ref "U2") (pin "18") (pinfunction "RCR5_18") (pintype "bidirectional"))
    )
    (net (code "34") (name "DVID_20") (class "Default")
      (node (ref "R23") (pin "1") (pinfunction "1_1") (pintype "unspecified"))
      (node (ref "U2") (pin "19") (pinfunction "RCR6_19") (pintype "bidirectional"))
    )
    (net (code "35") (name "DVID_21") (class "Default")
      (node (ref "R20") (pin "1") (pinfunction "1_1") (pintype "unspecified"))
      (node (ref "U2") (pin "20") (pinfunction "RCR7_20") (pintype "bidirectional"))
    )
    (net (code "36") (name "DVID_22") (class "Default")
      (node (ref "R21") (pin "1") (pinfunction "1_1") (pintype "unspecified"))
      (node (ref "U2") (pin "21") (pinfunction "RCR8_21") (pintype "bidirectional"))
    )
    (net (code "37") (name "DVID_23") (class "Default")
      (node (ref "R19") (pin "1") (pinfunction "1_1") (pintype "unspecified"))
      (node (ref "U2") (pin "22") (pinfunction "RCR9_22") (pintype "bidirectional"))
    )
    (net (code "38") (name "DVID_CLK") (class "Default")
      (node (ref "R30") (pin "1") (pinfunction "1_1") (pintype "unspecified"))
      (node (ref "U2") (pin "26") (pinfunction "CLK_26") (pintype "bidirectional"))
    )
    (net (code "39") (name "DVID_ENABLE") (class "Default")
      (node (ref "R27") (pin "1") (pinfunction "1_1") (pintype "unspecified+no_connect"))
    )
    (net (code "40") (name "DVID_HSYNC") (class "Default")
      (node (ref "R29") (pin "1") (pinfunction "1_1") (pintype "unspecified"))
      (node (ref "U3") (pin "1") (pinfunction "A_1") (pintype "unspecified"))
      (node (ref "U8") (pin "2") (pinfunction "CLK_2") (pintype "unspecified"))
    )
    (net (code "41") (name "DVID_VSYNC") (class "Default")
      (node (ref "R28") (pin "1") (pinfunction "1_1") (pintype "unspecified"))
      (node (ref "U6") (pin "1") (pinfunction "B_1") (pintype "unspecified"))
      (node (ref "U8") (pin "1") (pinfunction "CLR_1") (pintype "unspecified"))
      (node (ref "U8") (pin "10") (pinfunction "ENT_10") (pintype "unspecified"))
      (node (ref "U8") (pin "7") (pinfunction "ENP_7") (pintype "unspecified"))
    )
    (net (code "42") (name "GND") (class "Default")
      (node (ref "C1") (pin "1") (pinfunction "1_1") (pintype "unspecified"))
      (node (ref "C10") (pin "1") (pinfunction "1_1") (pintype "unspecified"))
      (node (ref "C11") (pin "1") (pinfunction "1_1") (pintype "unspecified"))
      (node (ref "C13") (pin "1") (pinfunction "1_1") (pintype "unspecified"))
      (node (ref "C14") (pin "1") (pinfunction "1_1") (pintype "unspecified"))
      (node (ref "C15") (pin "1") (pinfunction "1_1") (pintype "unspecified"))
      (node (ref "C16") (pin "1") (pinfunction "1_1") (pintype "unspecified"))
      (node (ref "C17") (pin "1") (pinfunction "1_1") (pintype "unspecified"))
      (node (ref "C18") (pin "1") (pinfunction "1_1") (pintype "unspecified"))
      (node (ref "C19") (pin "1") (pinfunction "1_1") (pintype "unspecified"))
      (node (ref "C2") (pin "1") (pinfunction "1_1") (pintype "unspecified"))
      (node (ref "C3") (pin "1") (pinfunction "1_1") (pintype "unspecified"))
      (node (ref "C4") (pin "1") (pinfunction "1_1") (pintype "unspecified"))
      (node (ref "C5") (pin "1") (pinfunction "1_1") (pintype "unspecified"))
      (node (ref "C6") (pin "1") (pinfunction "1_1") (pintype "unspecified"))
      (node (ref "C7") (pin "1") (pinfunction "1_1") (pintype "unspecified"))
      (node (ref "C8") (pin "1") (pinfunction "1_1") (pintype "unspecified"))
      (node (ref "C9") (pin "1") (pinfunction "1_1") (pintype "unspecified"))
      (node (ref "J1") (pin "11") (pinfunction "11_11") (pintype "bidirectional"))
      (node (ref "J1") (pin "17") (pinfunction "17_17") (pintype "bidirectional"))
      (node (ref "J1") (pin "2") (pinfunction "2_2") (pintype "bidirectional"))
      (node (ref "J1") (pin "5") (pinfunction "5_5") (pintype "bidirectional"))
      (node (ref "J1") (pin "8") (pinfunction "8_8") (pintype "bidirectional"))
      (node (ref "J2") (pin "5") (pinfunction "GND_5") (pintype "unspecified"))
      (node (ref "J2") (pin "6") (pinfunction "EH_6") (pintype "unspecified"))
      (node (ref "J3") (pin "5") (pinfunction "5_5") (pintype "bidirectional"))
      (node (ref "Q1") (pin "1") (pinfunction "G_1") (pintype "unspecified"))
      (node (ref "Q2") (pin "2") (pinfunction "S_2") (pintype "unspecified"))
      (node (ref "R36") (pin "1") (pinfunction "1_1") (pintype "unspecified"))
      (node (ref "U1") (pin "1") (pinfunction "DFO_1") (pintype "unspecified"))
      (node (ref "U1") (pin "101") (pinfunction "PAD_101") (pintype "unspecified"))
      (node (ref "U1") (pin "19") (pinfunction "OGND_19") (pintype "unspecified"))
      (node (ref "U1") (pin "28") (pinfunction "OGND_28") (pintype "unspecified"))
      (node (ref "U1") (pin "39") (pinfunction "GND_39") (pintype "unspecified"))
      (node (ref "U1") (pin "4") (pinfunction "PIXS_4") (pintype "unspecified"))
      (node (ref "U1") (pin "45") (pinfunction "OGND_45") (pintype "unspecified"))
      (node (ref "U1") (pin "5") (pinfunction "GND_5") (pintype "unspecified"))
      (node (ref "U1") (pin "58") (pinfunction "OGND_58") (pintype "unspecified"))
      (node (ref "U1") (pin "68") (pinfunction "GND_68") (pintype "unspecified"))
      (node (ref "U1") (pin "76") (pinfunction "OGND_76") (pintype "unspecified"))
      (node (ref "U1") (pin "79") (pinfunction "AGND_79") (pintype "unspecified"))
      (node (ref "U1") (pin "83") (pinfunction "AGND_83") (pintype "unspecified"))
      (node (ref "U1") (pin "87") (pinfunction "AGND_87") (pintype "unspecified"))
      (node (ref "U1") (pin "89") (pinfunction "AGND_89") (pintype "unspecified"))
      (node (ref "U1") (pin "92") (pinfunction "AGND_92") (pintype "unspecified"))
      (node (ref "U1") (pin "98") (pinfunction "PGND_98") (pintype "unspecified"))
      (node (ref "U2") (pin "10") (pinfunction "BCB0_10") (pintype "bidirectional"))
      (node (ref "U2") (pin "11") (pinfunction "DVSS_11") (pintype "bidirectional"))
      (node (ref "U2") (pin "13") (pinfunction "RCR0_13") (pintype "bidirectional"))
      (node (ref "U2") (pin "14") (pinfunction "RCR1_14") (pintype "bidirectional"))
      (node (ref "U2") (pin "25") (pinfunction "SYNC_T_25") (pintype "bidirectional"))
      (node (ref "U2") (pin "35") (pinfunction "GY1_35") (pintype "bidirectional"))
      (node (ref "U2") (pin "36") (pinfunction "GY0_36") (pintype "bidirectional"))
      (node (ref "U2") (pin "42") (pinfunction "AVSS_1_42") (pintype "bidirectional"))
      (node (ref "U2") (pin "46") (pinfunction "AVSS_2_46") (pintype "bidirectional"))
      (node (ref "U2") (pin "49") (pinfunction "THERMAL_PAD_49") (pintype "bidirectional"))
      (node (ref "U2") (pin "9") (pinfunction "BCB1_9") (pintype "bidirectional"))
      (node (ref "U3") (pin "3") (pinfunction "GND_3") (pintype "unspecified"))
      (node (ref "U4") (pin "2") (pinfunction "GND_2") (pintype "passive"))
      (node (ref "U5") (pin "1") (pinfunction "GND_1") (pintype "unspecified"))
      (node (ref "U6") (pin "3") (pinfunction "GND_3") (pintype "unspecified"))
      (node (ref "U7") (pin "3") (pinfunction "GND_3") (pintype "unspecified"))
      (node (ref "U8") (pin "3") (pinfunction "A_3") (pintype "unspecified"))
      (node (ref "U8") (pin "4") (pinfunction "B_4") (pintype "unspecified"))
      (node (ref "U8") (pin "5") (pinfunction "C_5") (pintype "unspecified"))
      (node (ref "U8") (pin "6") (pinfunction "D_6") (pintype "unspecified"))
      (node (ref "U8") (pin "8") (pinfunction "GND_8") (pintype "unspecified"))
    )
    (net (code "43") (name "M1") (class "Default")
      (node (ref "U2") (pin "48") (pinfunction "M2_48") (pintype "bidirectional"))
    )
    (net (code "44") (name "M2") (class "Default")
      (node (ref "U2") (pin "47") (pinfunction "M1_47") (pintype "bidirectional"))
    )
    (net (code "45") (name "Net-(J1-Pad19)") (class "Default")
      (node (ref "J1") (pin "19") (pinfunction "19_19") (pintype "bidirectional"))
      (node (ref "R2") (pin "2") (pinfunction "2_2") (pintype "unspecified"))
    )
    (net (code "46") (name "Net-(LED1-Pad1)") (class "Default")
      (node (ref "LED1") (pin "1") (pinfunction "1_1") (pintype "unspecified"))
      (node (ref "R37") (pin "2") (pinfunction "2_2") (pintype "unspecified"))
    )
    (net (code "47") (name "Net-(Q2-D)") (class "Default")
      (node (ref "LED1") (pin "2") (pinfunction "2_2") (pintype "unspecified"))
      (node (ref "Q2") (pin "3") (pinfunction "D_3") (pintype "unspecified"))
    )
    (net (code "48") (name "Net-(U1-DE)") (class "Default")
      (node (ref "R27") (pin "2") (pinfunction "2_2") (pintype "unspecified"))
      (node (ref "U1") (pin "46") (pinfunction "DE_46") (pintype "unspecified"))
    )
    (net (code "49") (name "Net-(U1-HSYNC)") (class "Default")
      (node (ref "R29") (pin "2") (pinfunction "2_2") (pintype "unspecified"))
      (node (ref "U1") (pin "48") (pinfunction "HSYNC_48") (pintype "unspecified"))
    )
    (net (code "50") (name "Net-(U1-OCK_INV)") (class "Default")
      (node (ref "R31") (pin "1") (pinfunction "1_1") (pintype "unspecified"))
      (node (ref "U1") (pin "100") (pinfunction "OCK_INV_100") (pintype "unspecified"))
    )
    (net (code "51") (name "Net-(U1-ODCK)") (class "Default")
      (node (ref "R30") (pin "2") (pinfunction "2_2") (pintype "unspecified"))
      (node (ref "U1") (pin "44") (pinfunction "ODCK_44") (pintype "unspecified"))
    )
    (net (code "52") (name "Net-(U1-PD#)") (class "Default")
      (node (ref "D1") (pin "1") (pinfunction "1_1") (pintype "unspecified"))
      (node (ref "U1") (pin "2") (pinfunction "PD#_2") (pintype "unspecified"))
    )
    (net (code "53") (name "Net-(U1-PDO#)") (class "Default")
      (node (ref "D2") (pin "1") (pinfunction "1_1") (pintype "unspecified"))
      (node (ref "U1") (pin "9") (pinfunction "PDO#_9") (pintype "unspecified"))
    )
    (net (code "54") (name "Net-(U1-QE0)") (class "Default")
      (node (ref "R3") (pin "2") (pinfunction "2_2") (pintype "unspecified"))
      (node (ref "U1") (pin "10") (pinfunction "QE0_10") (pintype "unspecified"))
    )
    (net (code "55") (name "Net-(U1-QE1)") (class "Default")
      (node (ref "R4") (pin "2") (pinfunction "2_2") (pintype "unspecified"))
      (node (ref "U1") (pin "11") (pinfunction "QE1_11") (pintype "unspecified"))
    )
    (net (code "56") (name "Net-(U1-QE2)") (class "Default")
      (node (ref "R5") (pin "2") (pinfunction "2_2") (pintype "unspecified"))
      (node (ref "U1") (pin "12") (pinfunction "QE2_12") (pintype "unspecified"))
    )
    (net (code "57") (name "Net-(U1-QE3)") (class "Default")
      (node (ref "R7") (pin "2") (pinfunction "2_2") (pintype "unspecified"))
      (node (ref "U1") (pin "13") (pinfunction "QE3_13") (pintype "unspecified"))
    )
    (net (code "58") (name "Net-(U1-QE4)") (class "Default")
      (node (ref "R6") (pin "2") (pinfunction "2_2") (pintype "unspecified"))
      (node (ref "U1") (pin "14") (pinfunction "QE4_14") (pintype "unspecified"))
    )
    (net (code "59") (name "Net-(U1-QE5)") (class "Default")
      (node (ref "R9") (pin "2") (pinfunction "2_2") (pintype "unspecified"))
      (node (ref "U1") (pin "15") (pinfunction "QE5_15") (pintype "unspecified"))
    )
    (net (code "60") (name "Net-(U1-QE6)") (class "Default")
      (node (ref "R8") (pin "2") (pinfunction "2_2") (pintype "unspecified"))
      (node (ref "U1") (pin "16") (pinfunction "QE6_16") (pintype "unspecified"))
    )
    (net (code "61") (name "Net-(U1-QE7)") (class "Default")
      (node (ref "R10") (pin "2") (pinfunction "2_2") (pintype "unspecified"))
      (node (ref "U1") (pin "17") (pinfunction "QE7_17") (pintype "unspecified"))
    )
    (net (code "62") (name "Net-(U1-QE8)") (class "Default")
      (node (ref "R18") (pin "2") (pinfunction "2_2") (pintype "unspecified"))
      (node (ref "U1") (pin "20") (pinfunction "QE8_20") (pintype "unspecified"))
    )
    (net (code "63") (name "Net-(U1-QE9)") (class "Default")
      (node (ref "R17") (pin "2") (pinfunction "2_2") (pintype "unspecified"))
      (node (ref "U1") (pin "21") (pinfunction "QE9_21") (pintype "unspecified"))
    )
    (net (code "64") (name "Net-(U1-QE10)") (class "Default")
      (node (ref "R16") (pin "2") (pinfunction "2_2") (pintype "unspecified"))
      (node (ref "U1") (pin "22") (pinfunction "QE10_22") (pintype "unspecified"))
    )
    (net (code "65") (name "Net-(U1-QE11)") (class "Default")
      (node (ref "R14") (pin "2") (pinfunction "2_2") (pintype "unspecified"))
      (node (ref "U1") (pin "23") (pinfunction "QE11_23") (pintype "unspecified"))
    )
    (net (code "66") (name "Net-(U1-QE12)") (class "Default")
      (node (ref "R15") (pin "2") (pinfunction "2_2") (pintype "unspecified"))
      (node (ref "U1") (pin "24") (pinfunction "QE12_24") (pintype "unspecified"))
    )
    (net (code "67") (name "Net-(U1-QE13)") (class "Default")
      (node (ref "R12") (pin "2") (pinfunction "2_2") (pintype "unspecified"))
      (node (ref "U1") (pin "25") (pinfunction "QE13_25") (pintype "unspecified"))
    )
    (net (code "68") (name "Net-(U1-QE14)") (class "Default")
      (node (ref "R13") (pin "2") (pinfunction "2_2") (pintype "unspecified"))
      (node (ref "U1") (pin "26") (pinfunction "QE14_26") (pintype "unspecified"))
    )
    (net (code "69") (name "Net-(U1-QE15)") (class "Default")
      (node (ref "R11") (pin "2") (pinfunction "2_2") (pintype "unspecified"))
      (node (ref "U1") (pin "27") (pinfunction "QE15_27") (pintype "unspecified"))
    )
    (net (code "70") (name "Net-(U1-QE16)") (class "Default")
      (node (ref "R26") (pin "2") (pinfunction "2_2") (pintype "unspecified"))
      (node (ref "U1") (pin "30") (pinfunction "QE16_30") (pintype "unspecified"))
    )
    (net (code "71") (name "Net-(U1-QE17)") (class "Default")
      (node (ref "R25") (pin "2") (pinfunction "2_2") (pintype "unspecified"))
      (node (ref "U1") (pin "31") (pinfunction "QE17_31") (pintype "unspecified"))
    )
    (net (code "72") (name "Net-(U1-QE18)") (class "Default")
      (node (ref "R24") (pin "2") (pinfunction "2_2") (pintype "unspecified"))
      (node (ref "U1") (pin "32") (pinfunction "QE18_32") (pintype "unspecified"))
    )
    (net (code "73") (name "Net-(U1-QE19)") (class "Default")
      (node (ref "R22") (pin "2") (pinfunction "2_2") (pintype "unspecified"))
      (node (ref "U1") (pin "33") (pinfunction "QE19_33") (pintype "unspecified"))
    )
    (net (code "74") (name "Net-(U1-QE20)") (class "Default")
      (node (ref "R23") (pin "2") (pinfunction "2_2") (pintype "unspecified"))
      (node (ref "U1") (pin "34") (pinfunction "QE20_34") (pintype "unspecified"))
    )
    (net (code "75") (name "Net-(U1-QE21)") (class "Default")
      (node (ref "R20") (pin "2") (pinfunction "2_2") (pintype "unspecified"))
      (node (ref "U1") (pin "35") (pinfunction "QE21_35") (pintype "unspecified"))
    )
    (net (code "76") (name "Net-(U1-QE22)") (class "Default")
      (node (ref "R21") (pin "2") (pinfunction "2_2") (pintype "unspecified"))
      (node (ref "U1") (pin "36") (pinfunction "QE22_36") (pintype "unspecified"))
    )
    (net (code "77") (name "Net-(U1-QE23)") (class "Default")
      (node (ref "R19") (pin "2") (pinfunction "2_2") (pintype "unspecified"))
      (node (ref "U1") (pin "37") (pinfunction "QE23_37") (pintype "unspecified"))
    )
    (net (code "78") (name "Net-(U1-ST)") (class "Default")
      (node (ref "R1") (pin "1") (pinfunction "1_1") (pintype "unspecified"))
      (node (ref "U1") (pin "3") (pinfunction "ST_3") (pintype "unspecified"))
    )
    (net (code "79") (name "Net-(U1-VSYNC)") (class "Default")
      (node (ref "R28") (pin "2") (pinfunction "2_2") (pintype "unspecified"))
      (node (ref "U1") (pin "47") (pinfunction "VSYNC_47") (pintype "unspecified"))
    )
    (net (code "80") (name "Net-(U2-COMP)") (class "Default")
      (node (ref "C12") (pin "1") (pinfunction "1_1") (pintype "unspecified"))
      (node (ref "U2") (pin "39") (pinfunction "COMP_39") (pintype "bidirectional"))
    )
    (net (code "81") (name "Net-(U2-FSADJ)") (class "Default")
      (node (ref "R36") (pin "2") (pinfunction "2_2") (pintype "unspecified"))
      (node (ref "U2") (pin "38") (pinfunction "FSADJ_38") (pintype "bidirectional"))
    )
    (net (code "82") (name "Net-(U3-B)") (class "Default")
      (node (ref "U3") (pin "2") (pinfunction "B_2") (pintype "unspecified"))
      (node (ref "U6") (pin "4") (pinfunction "Y_4") (pintype "unspecified"))
    )
    (net (code "83") (name "Net-(U7-A)") (class "Default")
      (node (ref "U7") (pin "1") (pinfunction "A_1") (pintype "unspecified"))
      (node (ref "U8") (pin "12") (pinfunction "QC_12") (pintype "unspecified"))
    )
    (net (code "84") (name "Net-(U7-B)") (class "Default")
      (node (ref "U7") (pin "2") (pinfunction "B_2") (pintype "unspecified"))
      (node (ref "U8") (pin "11") (pinfunction "QD_11") (pintype "unspecified"))
    )
    (net (code "85") (name "OVDD") (class "Default")
      (node (ref "C3") (pin "2") (pinfunction "2_2") (pintype "unspecified"))
      (node (ref "C4") (pin "2") (pinfunction "2_2") (pintype "unspecified"))
      (node (ref "C5") (pin "2") (pinfunction "2_2") (pintype "unspecified"))
      (node (ref "C6") (pin "2") (pinfunction "2_2") (pintype "unspecified"))
      (node (ref "L3") (pin "1") (pinfunction "1_1") (pintype "unspecified"))
      (node (ref "U1") (pin "18") (pinfunction "OVDD_18") (pintype "unspecified"))
      (node (ref "U1") (pin "29") (pinfunction "OVDD_29") (pintype "unspecified"))
      (node (ref "U1") (pin "43") (pinfunction "OVDD_43") (pintype "unspecified"))
      (node (ref "U1") (pin "57") (pinfunction "OVDD_57") (pintype "unspecified"))
      (node (ref "U1") (pin "78") (pinfunction "OVDD_78") (pintype "unspecified"))
    )
    (net (code "86") (name "PVDD") (class "Default")
      (node (ref "C9") (pin "2") (pinfunction "2_2") (pintype "unspecified"))
      (node (ref "L4") (pin "1") (pinfunction "1_1") (pintype "unspecified"))
      (node (ref "U1") (pin "97") (pinfunction "PVDD_97") (pintype "unspecified"))
    )
    (net (code "87") (name "PWR_ON") (class "Default")
      (node (ref "D1") (pin "2") (pinfunction "2_2") (pintype "unspecified"))
      (node (ref "D2") (pin "2") (pinfunction "2_2") (pintype "unspecified"))
    )
    (net (code "88") (name "SCL") (class "Default")
      (node (ref "J1") (pin "15") (pinfunction "15_15") (pintype "bidirectional"))
      (node (ref "R35") (pin "2") (pinfunction "2_2") (pintype "unspecified"))
    )
    (net (code "89") (name "SDA") (class "Default")
      (node (ref "J1") (pin "16") (pinfunction "16_16") (pintype "bidirectional"))
      (node (ref "R34") (pin "2") (pinfunction "2_2") (pintype "unspecified"))
    )
    (net (code "90") (name "SYNC") (class "Default")
      (node (ref "U2") (pin "24") (pinfunction "!SYNC_24") (pintype "bidirectional"))
      (node (ref "U3") (pin "4") (pinfunction "Y_4") (pintype "unspecified"))
    )
    (net (code "91") (name "TX0+") (class "Default")
      (node (ref "J1") (pin "7") (pinfunction "7_7") (pintype "bidirectional"))
      (node (ref "U1") (pin "90") (pinfunction "Rx0+_90") (pintype "unspecified"))
    )
    (net (code "92") (name "TX0-") (class "Default")
      (node (ref "J1") (pin "9") (pinfunction "9_9") (pintype "bidirectional"))
      (node (ref "U1") (pin "91") (pinfunction "Rx0-_91") (pintype "unspecified"))
    )
    (net (code "93") (name "TX1+") (class "Default")
      (node (ref "J1") (pin "4") (pinfunction "4_4") (pintype "bidirectional"))
      (node (ref "U1") (pin "85") (pinfunction "Rx1+_85") (pintype "unspecified"))
    )
    (net (code "94") (name "TX1-") (class "Default")
      (node (ref "J1") (pin "6") (pinfunction "6_6") (pintype "bidirectional"))
      (node (ref "U1") (pin "86") (pinfunction "Rx1-_86") (pintype "unspecified"))
    )
    (net (code "95") (name "TX2+") (class "Default")
      (node (ref "J1") (pin "1") (pinfunction "1_1") (pintype "bidirectional"))
      (node (ref "U1") (pin "80") (pinfunction "Rx2+_80") (pintype "unspecified"))
    )
    (net (code "96") (name "TX2-") (class "Default")
      (node (ref "J1") (pin "3") (pinfunction "3_3") (pintype "bidirectional"))
      (node (ref "U1") (pin "81") (pinfunction "Rx2-_81") (pintype "unspecified"))
    )
    (net (code "97") (name "TXC+") (class "Default")
      (node (ref "J1") (pin "10") (pinfunction "10_10") (pintype "bidirectional"))
      (node (ref "U1") (pin "93") (pinfunction "RxC+_93") (pintype "unspecified"))
    )
    (net (code "98") (name "TXC-") (class "Default")
      (node (ref "J1") (pin "12") (pinfunction "12_12") (pintype "bidirectional"))
      (node (ref "U1") (pin "94") (pinfunction "RxC-_94") (pintype "unspecified"))
    )
    (net (code "99") (name "unconnected-(J1-Pad13)") (class "Default")
      (node (ref "J1") (pin "13") (pinfunction "13_13") (pintype "bidirectional+no_connect"))
    )
    (net (code "100") (name "unconnected-(J1-Pad14)") (class "Default")
      (node (ref "J1") (pin "14") (pinfunction "14_14") (pintype "bidirectional+no_connect"))
    )
    (net (code "101") (name "unconnected-(J1-PadMH1)") (class "Default")
      (node (ref "J1") (pin "MH1") (pinfunction "MH1_MH1") (pintype "unspecified"))
    )
    (net (code "102") (name "unconnected-(J1-PadMH2)") (class "Default")
      (node (ref "J1") (pin "MH2") (pinfunction "MH2_MH2") (pintype "bidirectional"))
    )
    (net (code "103") (name "unconnected-(J1-PadMH3)") (class "Default")
      (node (ref "J1") (pin "MH3") (pinfunction "MH3_MH3") (pintype "bidirectional"))
    )
    (net (code "104") (name "unconnected-(J1-PadMH4)") (class "Default")
      (node (ref "J1") (pin "MH4") (pinfunction "MH4_MH4") (pintype "bidirectional"))
    )
    (net (code "105") (name "unconnected-(J2-D+-Pad3)") (class "Default")
      (node (ref "J2") (pin "3") (pinfunction "D+_3") (pintype "unspecified+no_connect"))
    )
    (net (code "106") (name "unconnected-(J2-D--Pad2)") (class "Default")
      (node (ref "J2") (pin "2") (pinfunction "D-_2") (pintype "unspecified+no_connect"))
    )
    (net (code "107") (name "unconnected-(J2-IO-Pad4)") (class "Default")
      (node (ref "J2") (pin "4") (pinfunction "IO_4") (pintype "unspecified+no_connect"))
    )
    (net (code "108") (name "unconnected-(U1-CTL1-Pad40)") (class "Default")
      (node (ref "U1") (pin "40") (pinfunction "CTL1_40") (pintype "unspecified+no_connect"))
    )
    (net (code "109") (name "unconnected-(U1-CTL2-Pad41)") (class "Default")
      (node (ref "U1") (pin "41") (pinfunction "CTL2_41") (pintype "unspecified+no_connect"))
    )
    (net (code "110") (name "unconnected-(U1-CTL3-Pad42)") (class "Default")
      (node (ref "U1") (pin "42") (pinfunction "CTL3_42") (pintype "unspecified+no_connect"))
    )
    (net (code "111") (name "unconnected-(U1-EXT_RES-Pad96)") (class "Default")
      (node (ref "U1") (pin "96") (pinfunction "EXT_RES_96") (pintype "unspecified+no_connect"))
    )
    (net (code "112") (name "unconnected-(U1-QO0-Pad49)") (class "Default")
      (node (ref "U1") (pin "49") (pinfunction "QO0_49") (pintype "unspecified+no_connect"))
    )
    (net (code "113") (name "unconnected-(U1-QO1-Pad50)") (class "Default")
      (node (ref "U1") (pin "50") (pinfunction "QO1_50") (pintype "unspecified+no_connect"))
    )
    (net (code "114") (name "unconnected-(U1-QO2-Pad51)") (class "Default")
      (node (ref "U1") (pin "51") (pinfunction "QO2_51") (pintype "unspecified+no_connect"))
    )
    (net (code "115") (name "unconnected-(U1-QO3-Pad52)") (class "Default")
      (node (ref "U1") (pin "52") (pinfunction "QO3_52") (pintype "unspecified+no_connect"))
    )
    (net (code "116") (name "unconnected-(U1-QO4-Pad53)") (class "Default")
      (node (ref "U1") (pin "53") (pinfunction "QO4_53") (pintype "unspecified+no_connect"))
    )
    (net (code "117") (name "unconnected-(U1-QO5-Pad54)") (class "Default")
      (node (ref "U1") (pin "54") (pinfunction "QO5_54") (pintype "unspecified+no_connect"))
    )
    (net (code "118") (name "unconnected-(U1-QO6-Pad55)") (class "Default")
      (node (ref "U1") (pin "55") (pinfunction "QO6_55") (pintype "unspecified+no_connect"))
    )
    (net (code "119") (name "unconnected-(U1-QO7-Pad56)") (class "Default")
      (node (ref "U1") (pin "56") (pinfunction "QO7_56") (pintype "unspecified+no_connect"))
    )
    (net (code "120") (name "unconnected-(U1-QO8-Pad59)") (class "Default")
      (node (ref "U1") (pin "59") (pinfunction "QO8_59") (pintype "unspecified+no_connect"))
    )
    (net (code "121") (name "unconnected-(U1-QO9-Pad60)") (class "Default")
      (node (ref "U1") (pin "60") (pinfunction "QO9_60") (pintype "unspecified+no_connect"))
    )
    (net (code "122") (name "unconnected-(U1-QO10-Pad61)") (class "Default")
      (node (ref "U1") (pin "61") (pinfunction "QO10_61") (pintype "unspecified+no_connect"))
    )
    (net (code "123") (name "unconnected-(U1-QO11-Pad62)") (class "Default")
      (node (ref "U1") (pin "62") (pinfunction "QO11_62") (pintype "unspecified+no_connect"))
    )
    (net (code "124") (name "unconnected-(U1-QO12-Pad63)") (class "Default")
      (node (ref "U1") (pin "63") (pinfunction "QO12_63") (pintype "unspecified+no_connect"))
    )
    (net (code "125") (name "unconnected-(U1-QO13-Pad64)") (class "Default")
      (node (ref "U1") (pin "64") (pinfunction "QO13_64") (pintype "unspecified+no_connect"))
    )
    (net (code "126") (name "unconnected-(U1-QO14-Pad65)") (class "Default")
      (node (ref "U1") (pin "65") (pinfunction "QO14_65") (pintype "unspecified+no_connect"))
    )
    (net (code "127") (name "unconnected-(U1-QO15-Pad66)") (class "Default")
      (node (ref "U1") (pin "66") (pinfunction "QO15_66") (pintype "unspecified+no_connect"))
    )
    (net (code "128") (name "unconnected-(U1-QO16-Pad69)") (class "Default")
      (node (ref "U1") (pin "69") (pinfunction "QO16_69") (pintype "unspecified+no_connect"))
    )
    (net (code "129") (name "unconnected-(U1-QO17-Pad70)") (class "Default")
      (node (ref "U1") (pin "70") (pinfunction "QO17_70") (pintype "unspecified+no_connect"))
    )
    (net (code "130") (name "unconnected-(U1-QO18-Pad71)") (class "Default")
      (node (ref "U1") (pin "71") (pinfunction "QO18_71") (pintype "unspecified+no_connect"))
    )
    (net (code "131") (name "unconnected-(U1-QO19-Pad72)") (class "Default")
      (node (ref "U1") (pin "72") (pinfunction "QO19_72") (pintype "unspecified+no_connect"))
    )
    (net (code "132") (name "unconnected-(U1-QO20-Pad73)") (class "Default")
      (node (ref "U1") (pin "73") (pinfunction "QO20_73") (pintype "unspecified+no_connect"))
    )
    (net (code "133") (name "unconnected-(U1-QO21-Pad74)") (class "Default")
      (node (ref "U1") (pin "74") (pinfunction "QO21_74") (pintype "unspecified+no_connect"))
    )
    (net (code "134") (name "unconnected-(U1-QO22-Pad75)") (class "Default")
      (node (ref "U1") (pin "75") (pinfunction "QO22_75") (pintype "unspecified+no_connect"))
    )
    (net (code "135") (name "unconnected-(U1-QO23-Pad77)") (class "Default")
      (node (ref "U1") (pin "77") (pinfunction "QO23_77") (pintype "unspecified+no_connect"))
    )
    (net (code "136") (name "unconnected-(U2-!BLANK-Pad23)") (class "Default")
      (node (ref "U2") (pin "23") (pinfunction "!BLANK_23") (pintype "bidirectional+no_connect"))
    )
    (net (code "137") (name "unconnected-(U8-QA-Pad14)") (class "Default")
      (node (ref "U8") (pin "14") (pinfunction "QA_14") (pintype "unspecified+no_connect"))
    )
    (net (code "138") (name "unconnected-(U8-QB-Pad13)") (class "Default")
      (node (ref "U8") (pin "13") (pinfunction "QB_13") (pintype "unspecified+no_connect"))
    )
    (net (code "139") (name "unconnected-(U8-RCO-Pad15)") (class "Default")
      (node (ref "U8") (pin "15") (pinfunction "RCO_15") (pintype "unspecified+no_connect"))
    )
  )
)
